# control_board.net
KiCad netlist of a schematic drawn in EAGLE
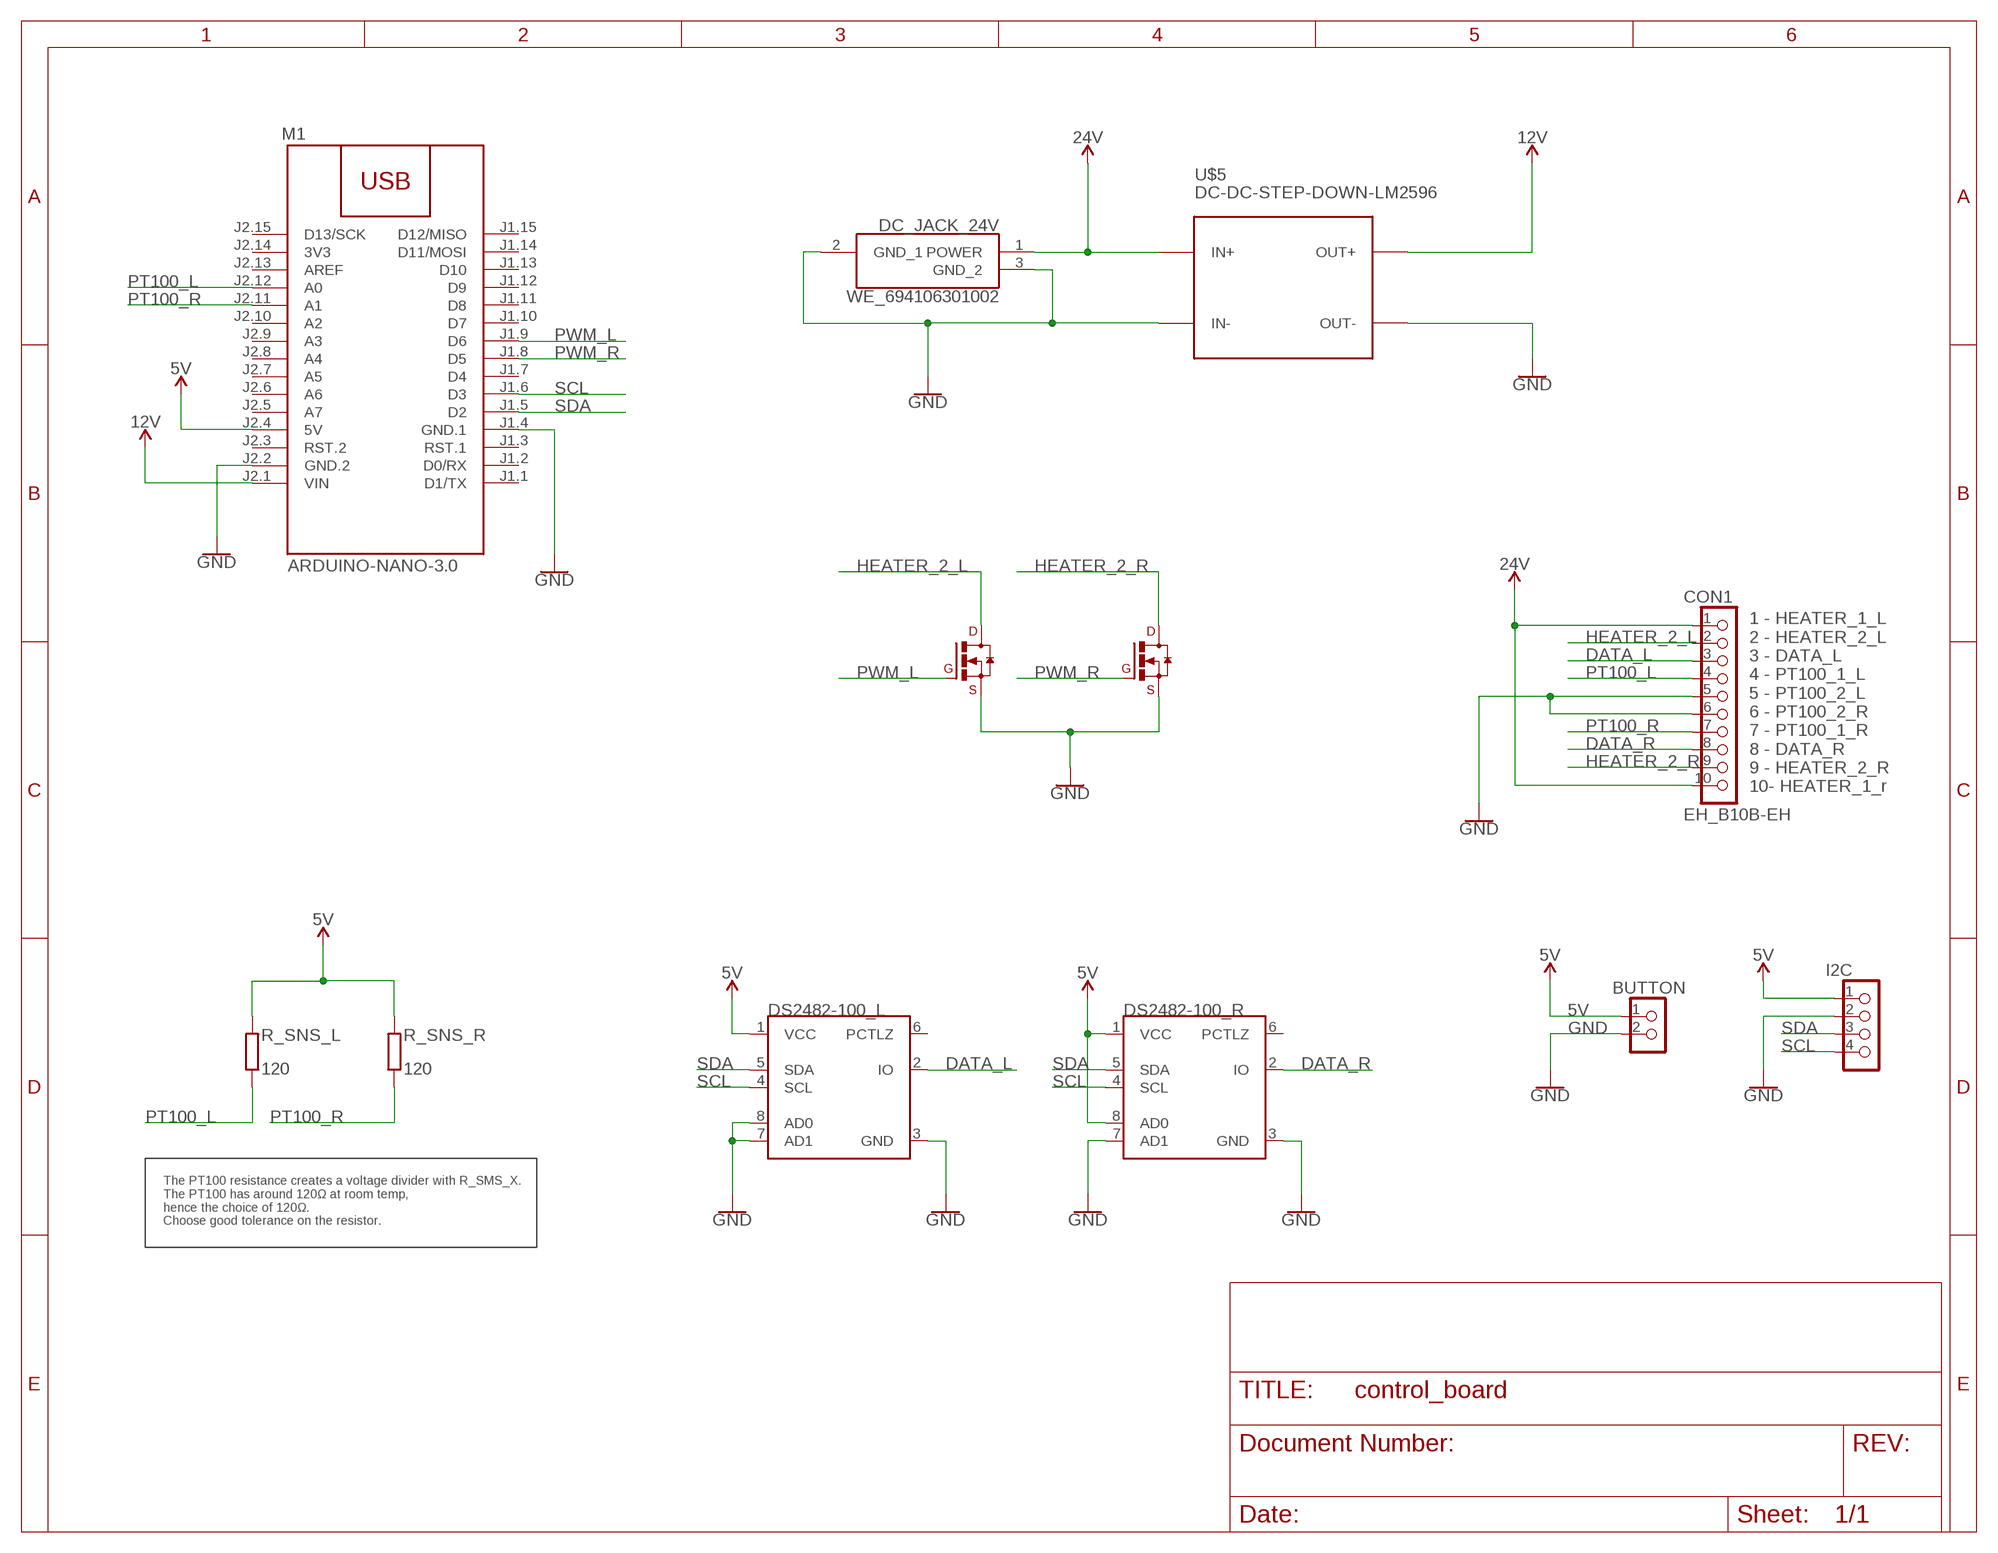
[diagram p0: schematic, sheet 1]

(export (version "E")
  (design (tool "Eeschema 10.0.6"))
  (components
    (comp (ref "BUTTON")
      (value "EH_B2B-EH")
      (footprint "eagle-import:B2B-EH")
      (libsource (lib "eagle-import") (part "EH_B2B-EH"))
    )
    (comp (ref "CON1")
      (value "EH_B10B-EH")
      (footprint "eagle-import:B10B-EH")
      (libsource (lib "eagle-import") (part "EH_B10B-EH"))
    )
    (comp (ref "DC_JACK_24V")
      (value "WE_694106301002")
      (footprint "eagle-import:WE_694106301002")
      (libsource (lib "eagle-import") (part "WE_694106301002"))
    )
    (comp (ref "DS2482-100_L")
      (value "DS2482-100")
      (footprint "eagle-import:SOIC127P600X175-8N")
      (libsource (lib "eagle-import") (part "DS2482-100"))
    )
    (comp (ref "DS2482-100_R")
      (value "DS2482-100")
      (footprint "eagle-import:SOIC127P600X175-8N")
      (libsource (lib "eagle-import") (part "DS2482-100"))
    )
    (comp (ref "I2C")
      (value "EH_B4B-EH")
      (footprint "eagle-import:B4B-EH")
      (libsource (lib "eagle-import") (part "EH_B4B-EH"))
    )
    (comp (ref "M1")
      (value "ARDUINO-NANO-3.0")
      (footprint "eagle-import:ARDUINO-NANO-3.0")
      (libsource (lib "eagle-import") (part "ARDUINO-NANO-3.0"))
    )
    (comp (ref "R_SNS_L")
      (value "120")
      (footprint "eagle-import:R1206")
      (libsource (lib "eagle-import") (part "R1206"))
    )
    (comp (ref "R_SNS_R")
      (value "120")
      (footprint "eagle-import:R1206")
      (libsource (lib "eagle-import") (part "R1206"))
    )
    (comp (ref "U$1")
      (value "DMG4496SSS")
      (footprint "eagle-import:SOIC127P600X175-8N")
      (libsource (lib "eagle-import") (part "DMG4496SSS"))
    )
    (comp (ref "U$2")
      (value "DMG4496SSS")
      (footprint "eagle-import:SOIC127P600X175-8N")
      (libsource (lib "eagle-import") (part "DMG4496SSS"))
    )
    (comp (ref "U$5")
      (value "DC-DC-STEP-DOWN-LM2596")
      (footprint "eagle-import:DC-DC-STEP-DOWN-LM2596")
      (libsource (lib "eagle-import") (part "DC-DC-STEP-DOWN-LM2596"))
    )
  )
  (nets
    (net (code "1") (name "/3V3") (class "Default")
      (node (ref "M1") (pin "J2.14") (pinfunction "3V3_J2.14") (pintype "power_in"))
    )
    (net (code "2") (name "/DATA_L") (class "Default")
      (node (ref "CON1") (pin "3") (pinfunction "3_3") (pintype "passive"))
      (node (ref "DS2482-100_L") (pin "2") (pinfunction "IO_2") (pintype "bidirectional"))
    )
    (net (code "3") (name "/DATA_R") (class "Default")
      (node (ref "CON1") (pin "8") (pinfunction "8_8") (pintype "passive"))
      (node (ref "DS2482-100_R") (pin "2") (pinfunction "IO_2") (pintype "bidirectional"))
    )
    (net (code "4") (name "/HEATER_2_L") (class "Default")
      (node (ref "CON1") (pin "2") (pinfunction "2_2") (pintype "passive"))
      (node (ref "U$1") (pin "5") (pinfunction "D_5") (pintype "passive"))
      (node (ref "U$1") (pin "6") (pinfunction "D_6") (pintype "passive"))
      (node (ref "U$1") (pin "7") (pinfunction "D_7") (pintype "passive"))
      (node (ref "U$1") (pin "8") (pinfunction "D_8") (pintype "passive"))
    )
    (net (code "5") (name "/HEATER_2_R") (class "Default")
      (node (ref "CON1") (pin "9") (pinfunction "9_9") (pintype "passive"))
      (node (ref "U$2") (pin "5") (pinfunction "D_5") (pintype "passive"))
      (node (ref "U$2") (pin "6") (pinfunction "D_6") (pintype "passive"))
      (node (ref "U$2") (pin "7") (pinfunction "D_7") (pintype "passive"))
      (node (ref "U$2") (pin "8") (pinfunction "D_8") (pintype "passive"))
    )
    (net (code "6") (name "/PT100_L") (class "Default")
      (node (ref "CON1") (pin "4") (pinfunction "4_4") (pintype "passive"))
      (node (ref "M1") (pin "J2.12") (pinfunction "A0_J2.12") (pintype "bidirectional"))
      (node (ref "R_SNS_L") (pin "1") (pinfunction "1_1") (pintype "passive"))
    )
    (net (code "7") (name "/PT100_R") (class "Default")
      (node (ref "CON1") (pin "7") (pinfunction "7_7") (pintype "passive"))
      (node (ref "M1") (pin "J2.11") (pinfunction "A1_J2.11") (pintype "bidirectional"))
      (node (ref "R_SNS_R") (pin "1") (pinfunction "1_1") (pintype "passive"))
    )
    (net (code "8") (name "/PWM_L") (class "Default")
      (node (ref "M1") (pin "J1.9") (pinfunction "D6_J1.9") (pintype "bidirectional"))
      (node (ref "U$1") (pin "4") (pinfunction "G_4") (pintype "passive"))
    )
    (net (code "9") (name "/PWM_R") (class "Default")
      (node (ref "M1") (pin "J1.8") (pinfunction "D5_J1.8") (pintype "bidirectional"))
      (node (ref "U$2") (pin "4") (pinfunction "G_4") (pintype "passive"))
    )
    (net (code "10") (name "/SCL") (class "Default")
      (node (ref "DS2482-100_L") (pin "4") (pinfunction "SCL_4") (pintype "bidirectional"))
      (node (ref "DS2482-100_R") (pin "4") (pinfunction "SCL_4") (pintype "bidirectional"))
      (node (ref "I2C") (pin "4") (pinfunction "4_4") (pintype "passive"))
      (node (ref "M1") (pin "J1.6") (pinfunction "D3_J1.6") (pintype "bidirectional"))
    )
    (net (code "11") (name "/SDA") (class "Default")
      (node (ref "DS2482-100_L") (pin "5") (pinfunction "SDA_5") (pintype "bidirectional"))
      (node (ref "DS2482-100_R") (pin "5") (pinfunction "SDA_5") (pintype "bidirectional"))
      (node (ref "I2C") (pin "3") (pinfunction "3_3") (pintype "passive"))
      (node (ref "M1") (pin "J1.5") (pinfunction "D2_J1.5") (pintype "bidirectional"))
    )
    (net (code "12") (name "5V") (class "Default")
      (node (ref "BUTTON") (pin "1") (pinfunction "1_1") (pintype "passive"))
      (node (ref "DS2482-100_L") (pin "1") (pinfunction "VCC_1") (pintype "bidirectional"))
      (node (ref "DS2482-100_R") (pin "1") (pinfunction "VCC_1") (pintype "bidirectional"))
      (node (ref "DS2482-100_R") (pin "8") (pinfunction "AD0_8") (pintype "bidirectional"))
      (node (ref "I2C") (pin "1") (pinfunction "1_1") (pintype "passive"))
      (node (ref "M1") (pin "J2.4") (pinfunction "5V_J2.4") (pintype "power_in"))
      (node (ref "R_SNS_L") (pin "2") (pinfunction "2_2") (pintype "passive"))
      (node (ref "R_SNS_R") (pin "2") (pinfunction "2_2") (pintype "passive"))
    )
    (net (code "13") (name "12V") (class "Default")
      (node (ref "M1") (pin "J2.1") (pinfunction "VIN_J2.1") (pintype "power_in"))
      (node (ref "U$5") (pin "OUT+") (pinfunction "OUT+_OUT+") (pintype "bidirectional"))
    )
    (net (code "14") (name "24V") (class "Default")
      (node (ref "CON1") (pin "1") (pinfunction "1_1") (pintype "passive"))
      (node (ref "CON1") (pin "10") (pinfunction "10_10") (pintype "passive"))
      (node (ref "DC_JACK_24V") (pin "1") (pinfunction "POWER_1") (pintype "bidirectional"))
      (node (ref "U$5") (pin "IN+") (pinfunction "IN+_IN+") (pintype "bidirectional"))
    )
    (net (code "15") (name "GND") (class "Default")
      (node (ref "BUTTON") (pin "2") (pinfunction "2_2") (pintype "passive"))
      (node (ref "CON1") (pin "5") (pinfunction "5_5") (pintype "passive"))
      (node (ref "CON1") (pin "6") (pinfunction "6_6") (pintype "passive"))
      (node (ref "DC_JACK_24V") (pin "2") (pinfunction "GND_1_2") (pintype "bidirectional"))
      (node (ref "DC_JACK_24V") (pin "3") (pinfunction "GND_2_3") (pintype "bidirectional"))
      (node (ref "DS2482-100_L") (pin "3") (pinfunction "GND_3") (pintype "bidirectional"))
      (node (ref "DS2482-100_L") (pin "7") (pinfunction "AD1_7") (pintype "bidirectional"))
      (node (ref "DS2482-100_L") (pin "8") (pinfunction "AD0_8") (pintype "bidirectional"))
      (node (ref "DS2482-100_R") (pin "3") (pinfunction "GND_3") (pintype "bidirectional"))
      (node (ref "DS2482-100_R") (pin "7") (pinfunction "AD1_7") (pintype "bidirectional"))
      (node (ref "I2C") (pin "2") (pinfunction "2_2") (pintype "passive"))
      (node (ref "M1") (pin "J1.4") (pinfunction "GND.1_J1.4") (pintype "power_in"))
      (node (ref "M1") (pin "J2.2") (pinfunction "GND.2_J2.2") (pintype "power_in"))
      (node (ref "U$1") (pin "1") (pinfunction "S_1") (pintype "passive"))
      (node (ref "U$1") (pin "2") (pinfunction "S_2") (pintype "passive"))
      (node (ref "U$1") (pin "3") (pinfunction "S_3") (pintype "passive"))
      (node (ref "U$2") (pin "1") (pinfunction "S_1") (pintype "passive"))
      (node (ref "U$2") (pin "2") (pinfunction "S_2") (pintype "passive"))
      (node (ref "U$2") (pin "3") (pinfunction "S_3") (pintype "passive"))
      (node (ref "U$5") (pin "IN-") (pinfunction "IN-_IN-") (pintype "bidirectional"))
      (node (ref "U$5") (pin "OUT-") (pinfunction "OUT-_OUT-") (pintype "bidirectional"))
    )
    (net (code "16") (name "unconnected-(DS2482-100_L-PCTLZ-Pad6)") (class "Default")
      (node (ref "DS2482-100_L") (pin "6") (pinfunction "PCTLZ_6") (pintype "bidirectional"))
    )
    (net (code "17") (name "unconnected-(DS2482-100_R-PCTLZ-Pad6)") (class "Default")
      (node (ref "DS2482-100_R") (pin "6") (pinfunction "PCTLZ_6") (pintype "bidirectional"))
    )
    (net (code "18") (name "unconnected-(M1-A2-PadJ2.10)") (class "Default")
      (node (ref "M1") (pin "J2.10") (pinfunction "A2_J2.10") (pintype "bidirectional"))
    )
    (net (code "19") (name "unconnected-(M1-A3-PadJ2.9)") (class "Default")
      (node (ref "M1") (pin "J2.9") (pinfunction "A3_J2.9") (pintype "bidirectional"))
    )
    (net (code "20") (name "unconnected-(M1-A4-PadJ2.8)") (class "Default")
      (node (ref "M1") (pin "J2.8") (pinfunction "A4_J2.8") (pintype "bidirectional"))
    )
    (net (code "21") (name "unconnected-(M1-A5-PadJ2.7)") (class "Default")
      (node (ref "M1") (pin "J2.7") (pinfunction "A5_J2.7") (pintype "bidirectional"))
    )
    (net (code "22") (name "unconnected-(M1-A6-PadJ2.6)") (class "Default")
      (node (ref "M1") (pin "J2.6") (pinfunction "A6_J2.6") (pintype "bidirectional"))
    )
    (net (code "23") (name "unconnected-(M1-A7-PadJ2.5)") (class "Default")
      (node (ref "M1") (pin "J2.5") (pinfunction "A7_J2.5") (pintype "bidirectional"))
    )
    (net (code "24") (name "unconnected-(M1-AREF-PadJ2.13)") (class "Default")
      (node (ref "M1") (pin "J2.13") (pinfunction "AREF_J2.13") (pintype "bidirectional"))
    )
    (net (code "25") (name "unconnected-(M1-D0{slash}RX-PadJ1.2)") (class "Default")
      (node (ref "M1") (pin "J1.2") (pinfunction "D0/RX_J1.2") (pintype "bidirectional"))
    )
    (net (code "26") (name "unconnected-(M1-D1{slash}TX-PadJ1.1)") (class "Default")
      (node (ref "M1") (pin "J1.1") (pinfunction "D1/TX_J1.1") (pintype "bidirectional"))
    )
    (net (code "27") (name "unconnected-(M1-D4-PadJ1.7)") (class "Default")
      (node (ref "M1") (pin "J1.7") (pinfunction "D4_J1.7") (pintype "bidirectional"))
    )
    (net (code "28") (name "unconnected-(M1-D7-PadJ1.10)") (class "Default")
      (node (ref "M1") (pin "J1.10") (pinfunction "D7_J1.10") (pintype "bidirectional"))
    )
    (net (code "29") (name "unconnected-(M1-D8-PadJ1.11)") (class "Default")
      (node (ref "M1") (pin "J1.11") (pinfunction "D8_J1.11") (pintype "bidirectional"))
    )
    (net (code "30") (name "unconnected-(M1-D9-PadJ1.12)") (class "Default")
      (node (ref "M1") (pin "J1.12") (pinfunction "D9_J1.12") (pintype "bidirectional"))
    )
    (net (code "31") (name "unconnected-(M1-D10-PadJ1.13)") (class "Default")
      (node (ref "M1") (pin "J1.13") (pinfunction "D10_J1.13") (pintype "bidirectional"))
    )
    (net (code "32") (name "unconnected-(M1-D11{slash}MOSI-PadJ1.14)") (class "Default")
      (node (ref "M1") (pin "J1.14") (pinfunction "D11/MOSI_J1.14") (pintype "bidirectional"))
    )
    (net (code "33") (name "unconnected-(M1-D12{slash}MISO-PadJ1.15)") (class "Default")
      (node (ref "M1") (pin "J1.15") (pinfunction "D12/MISO_J1.15") (pintype "bidirectional"))
    )
    (net (code "34") (name "unconnected-(M1-D13{slash}SCK-PadJ2.15)") (class "Default")
      (node (ref "M1") (pin "J2.15") (pinfunction "D13/SCK_J2.15") (pintype "bidirectional"))
    )
    (net (code "35") (name "unconnected-(M1-RST.1-PadJ1.3)") (class "Default")
      (node (ref "M1") (pin "J1.3") (pinfunction "RST.1_J1.3") (pintype "bidirectional"))
    )
    (net (code "36") (name "unconnected-(M1-RST.2-PadJ2.3)") (class "Default")
      (node (ref "M1") (pin "J2.3") (pinfunction "RST.2_J2.3") (pintype "bidirectional"))
    )
  )
)
